# RX-Super-Regenerative-VHF-2Transistor-Ri.net
KiCad netlist of a schematic drawn in EAGLE
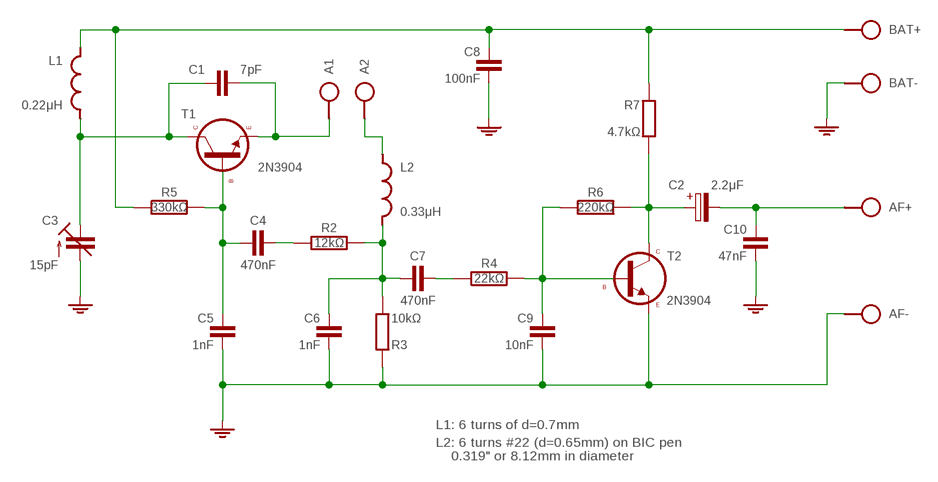
[diagram p0: schematic, sheet 1]

(export (version "E")
  (design (tool "Eeschema 10.0.6"))
  (components
    (comp (ref "A1")
      (value "SPAD")
      (footprint "eagle-import:SPAD")
      (libsource (lib "eagle-import") (part "SPAD"))
    )
    (comp (ref "A2")
      (value "SPAD")
      (footprint "eagle-import:SPAD")
      (libsource (lib "eagle-import") (part "SPAD"))
    )
    (comp (ref "AF+")
      (value "SPAD")
      (footprint "eagle-import:SPAD")
      (libsource (lib "eagle-import") (part "SPAD"))
    )
    (comp (ref "AF-")
      (value "SPAD")
      (footprint "eagle-import:SPAD")
      (libsource (lib "eagle-import") (part "SPAD"))
    )
    (comp (ref "BAT+")
      (value "SPAD")
      (footprint "eagle-import:SPAD")
      (libsource (lib "eagle-import") (part "SPAD"))
    )
    (comp (ref "BAT-")
      (value "SPAD")
      (footprint "eagle-import:SPAD")
      (libsource (lib "eagle-import") (part "SPAD"))
    )
    (comp (ref "C1")
      (value "7pF")
      (footprint "eagle-import:C050-020X036")
      (libsource (lib "eagle-import") (part "C050-020X036"))
    )
    (comp (ref "C2")
      (value "2.2μF")
      (footprint "eagle-import:E2,5-3")
      (libsource (lib "eagle-import") (part "CPOLE2,5-3"))
    )
    (comp (ref "C3")
      (value "15pF")
      (footprint "eagle-import:TRIM-2222-808")
      (libsource (lib "eagle-import") (part "C-TR-PH201272222-808-2PINB"))
    )
    (comp (ref "C4")
      (value "470nF")
      (footprint "eagle-import:C050-024X044_V")
      (libsource (lib "eagle-import") (part "C050-024X044/V"))
    )
    (comp (ref "C5")
      (value "1nF")
      (footprint "eagle-import:C025-020X036")
      (libsource (lib "eagle-import") (part "C025-020X036"))
    )
    (comp (ref "C6")
      (value "1nF")
      (footprint "eagle-import:C025-020X036")
      (libsource (lib "eagle-import") (part "C025-020X036"))
    )
    (comp (ref "C7")
      (value "470nF")
      (footprint "eagle-import:C050-024X044_V")
      (libsource (lib "eagle-import") (part "C050-024X044/V"))
    )
    (comp (ref "C8")
      (value "100nF")
      (footprint "eagle-import:C050-020X044")
      (libsource (lib "eagle-import") (part "C050-020X044"))
    )
    (comp (ref "C9")
      (value "10nF")
      (footprint "eagle-import:C025-015X024")
      (libsource (lib "eagle-import") (part "C025-015X024"))
    )
    (comp (ref "C10")
      (value "47nF")
      (footprint "eagle-import:C050-020X036_V")
      (libsource (lib "eagle-import") (part "C050-020X036/V"))
    )
    (comp (ref "L1")
      (value "0.22μH")
      (footprint "eagle-import:L-04-5_6V")
      (libsource (lib "eagle-import") (part "L-SHORT04-5/5V"))
    )
    (comp (ref "L2")
      (value "0.33μH")
      (footprint "eagle-import:L-08-5_8")
      (libsource (lib "eagle-import") (part "L-SHORTL-08-5/8"))
    )
    (comp (ref "R2")
      (value "12kΩ")
      (footprint "eagle-import:0202_7")
      (libsource (lib "eagle-import") (part "R-H0202/7"))
    )
    (comp (ref "R3")
      (value "10kΩ")
      (footprint "eagle-import:0202_5-V")
      (libsource (lib "eagle-import") (part "R0202/5-V"))
    )
    (comp (ref "R4")
      (value "22kΩ")
      (footprint "eagle-import:0202_7-V")
      (libsource (lib "eagle-import") (part "R-H0202/7-V"))
    )
    (comp (ref "R5")
      (value "330kΩ")
      (footprint "eagle-import:0202_7")
      (libsource (lib "eagle-import") (part "R-H0202/7"))
    )
    (comp (ref "R6")
      (value "220kΩ")
      (footprint "eagle-import:0202_7-V")
      (libsource (lib "eagle-import") (part "R-H0202/7-V"))
    )
    (comp (ref "R7")
      (value "4.7kΩ")
      (footprint "eagle-import:0202_7-V")
      (libsource (lib "eagle-import") (part "R0202/7-V"))
    )
    (comp (ref "T1")
      (value "2N3904")
      (footprint "eagle-import:TO92")
      (libsource (lib "eagle-import") (part "2N3904"))
    )
    (comp (ref "T2")
      (value "2N3904")
      (footprint "eagle-import:TO92")
      (libsource (lib "eagle-import") (part "2N3904"))
    )
  )
  (nets
    (net (code "1") (name "GND") (class "Default")
      (node (ref "AF-") (pin "1") (pinfunction "P$1_1") (pintype "passive"))
      (node (ref "BAT-") (pin "1") (pinfunction "P$1_1") (pintype "passive"))
      (node (ref "C10") (pin "2") (pinfunction "2_2") (pintype "passive"))
      (node (ref "C3") (pin "2") (pinfunction "A_2") (pintype "passive"))
      (node (ref "C5") (pin "2") (pinfunction "2_2") (pintype "passive"))
      (node (ref "C6") (pin "2") (pinfunction "2_2") (pintype "passive"))
      (node (ref "C8") (pin "2") (pinfunction "2_2") (pintype "passive"))
      (node (ref "C9") (pin "2") (pinfunction "2_2") (pintype "passive"))
      (node (ref "R3") (pin "1") (pinfunction "2_1") (pintype "passive"))
      (node (ref "T2") (pin "1") (pinfunction "E_1") (pintype "passive"))
    )
    (net (code "2") (name "Net-(A1-P$1)") (class "Default")
      (node (ref "A1") (pin "1") (pinfunction "P$1_1") (pintype "passive"))
      (node (ref "C1") (pin "1") (pinfunction "1_1") (pintype "passive"))
      (node (ref "T1") (pin "1") (pinfunction "E_1") (pintype "passive"))
    )
    (net (code "3") (name "Net-(A2-P$1)") (class "Default")
      (node (ref "A2") (pin "1") (pinfunction "P$1_1") (pintype "passive"))
      (node (ref "L2") (pin "2") (pinfunction "2_2") (pintype "passive"))
    )
    (net (code "4") (name "Net-(AF+-P$1)") (class "Default")
      (node (ref "AF+") (pin "1") (pinfunction "P$1_1") (pintype "passive"))
      (node (ref "C10") (pin "1") (pinfunction "1_1") (pintype "passive"))
      (node (ref "C2") (pin "-") (pinfunction "-_-") (pintype "passive"))
    )
    (net (code "5") (name "Net-(BAT+-P$1)") (class "Default")
      (node (ref "BAT+") (pin "1") (pinfunction "P$1_1") (pintype "passive"))
      (node (ref "C8") (pin "1") (pinfunction "1_1") (pintype "passive"))
      (node (ref "L1") (pin "1") (pinfunction "2_1") (pintype "passive"))
      (node (ref "R5") (pin "1") (pinfunction "1_1") (pintype "passive"))
      (node (ref "R7") (pin "1") (pinfunction "2_1") (pintype "passive"))
    )
    (net (code "6") (name "Net-(C3-E)") (class "Default")
      (node (ref "C1") (pin "2") (pinfunction "2_2") (pintype "passive"))
      (node (ref "C3") (pin "3") (pinfunction "E_3") (pintype "passive"))
      (node (ref "L1") (pin "2") (pinfunction "1_2") (pintype "passive"))
      (node (ref "T1") (pin "3") (pinfunction "C_3") (pintype "passive"))
    )
    (net (code "7") (name "Net-(C4-Pad1)") (class "Default")
      (node (ref "C4") (pin "1") (pinfunction "1_1") (pintype "passive"))
      (node (ref "R2") (pin "1") (pinfunction "1_1") (pintype "passive"))
    )
    (net (code "8") (name "Net-(C7-Pad1)") (class "Default")
      (node (ref "C7") (pin "1") (pinfunction "1_1") (pintype "passive"))
      (node (ref "R4") (pin "1") (pinfunction "1_1") (pintype "passive"))
    )
    (net (code "9") (name "Net-(R3-1)") (class "Default")
      (node (ref "C6") (pin "1") (pinfunction "1_1") (pintype "passive"))
      (node (ref "C7") (pin "2") (pinfunction "2_2") (pintype "passive"))
      (node (ref "L2") (pin "1") (pinfunction "1_1") (pintype "passive"))
      (node (ref "R2") (pin "2") (pinfunction "2_2") (pintype "passive"))
      (node (ref "R3") (pin "2") (pinfunction "1_2") (pintype "passive"))
    )
    (net (code "10") (name "Net-(R7-1)") (class "Default")
      (node (ref "C2") (pin "+") (pinfunction "+_+") (pintype "passive"))
      (node (ref "R6") (pin "2") (pinfunction "2_2") (pintype "passive"))
      (node (ref "R7") (pin "2") (pinfunction "1_2") (pintype "passive"))
      (node (ref "T2") (pin "3") (pinfunction "C_3") (pintype "passive"))
    )
    (net (code "11") (name "Net-(T1-B)") (class "Default")
      (node (ref "C4") (pin "2") (pinfunction "2_2") (pintype "passive"))
      (node (ref "C5") (pin "1") (pinfunction "1_1") (pintype "passive"))
      (node (ref "R5") (pin "2") (pinfunction "2_2") (pintype "passive"))
      (node (ref "T1") (pin "2") (pinfunction "B_2") (pintype "passive"))
    )
    (net (code "12") (name "Net-(T2-B)") (class "Default")
      (node (ref "C9") (pin "1") (pinfunction "1_1") (pintype "passive"))
      (node (ref "R4") (pin "2") (pinfunction "2_2") (pintype "passive"))
      (node (ref "R6") (pin "1") (pinfunction "1_1") (pintype "passive"))
      (node (ref "T2") (pin "2") (pinfunction "B_2") (pintype "passive"))
    )
  )
)
